# M7050X.net
KiCad netlist of a schematic drawn in EAGLE
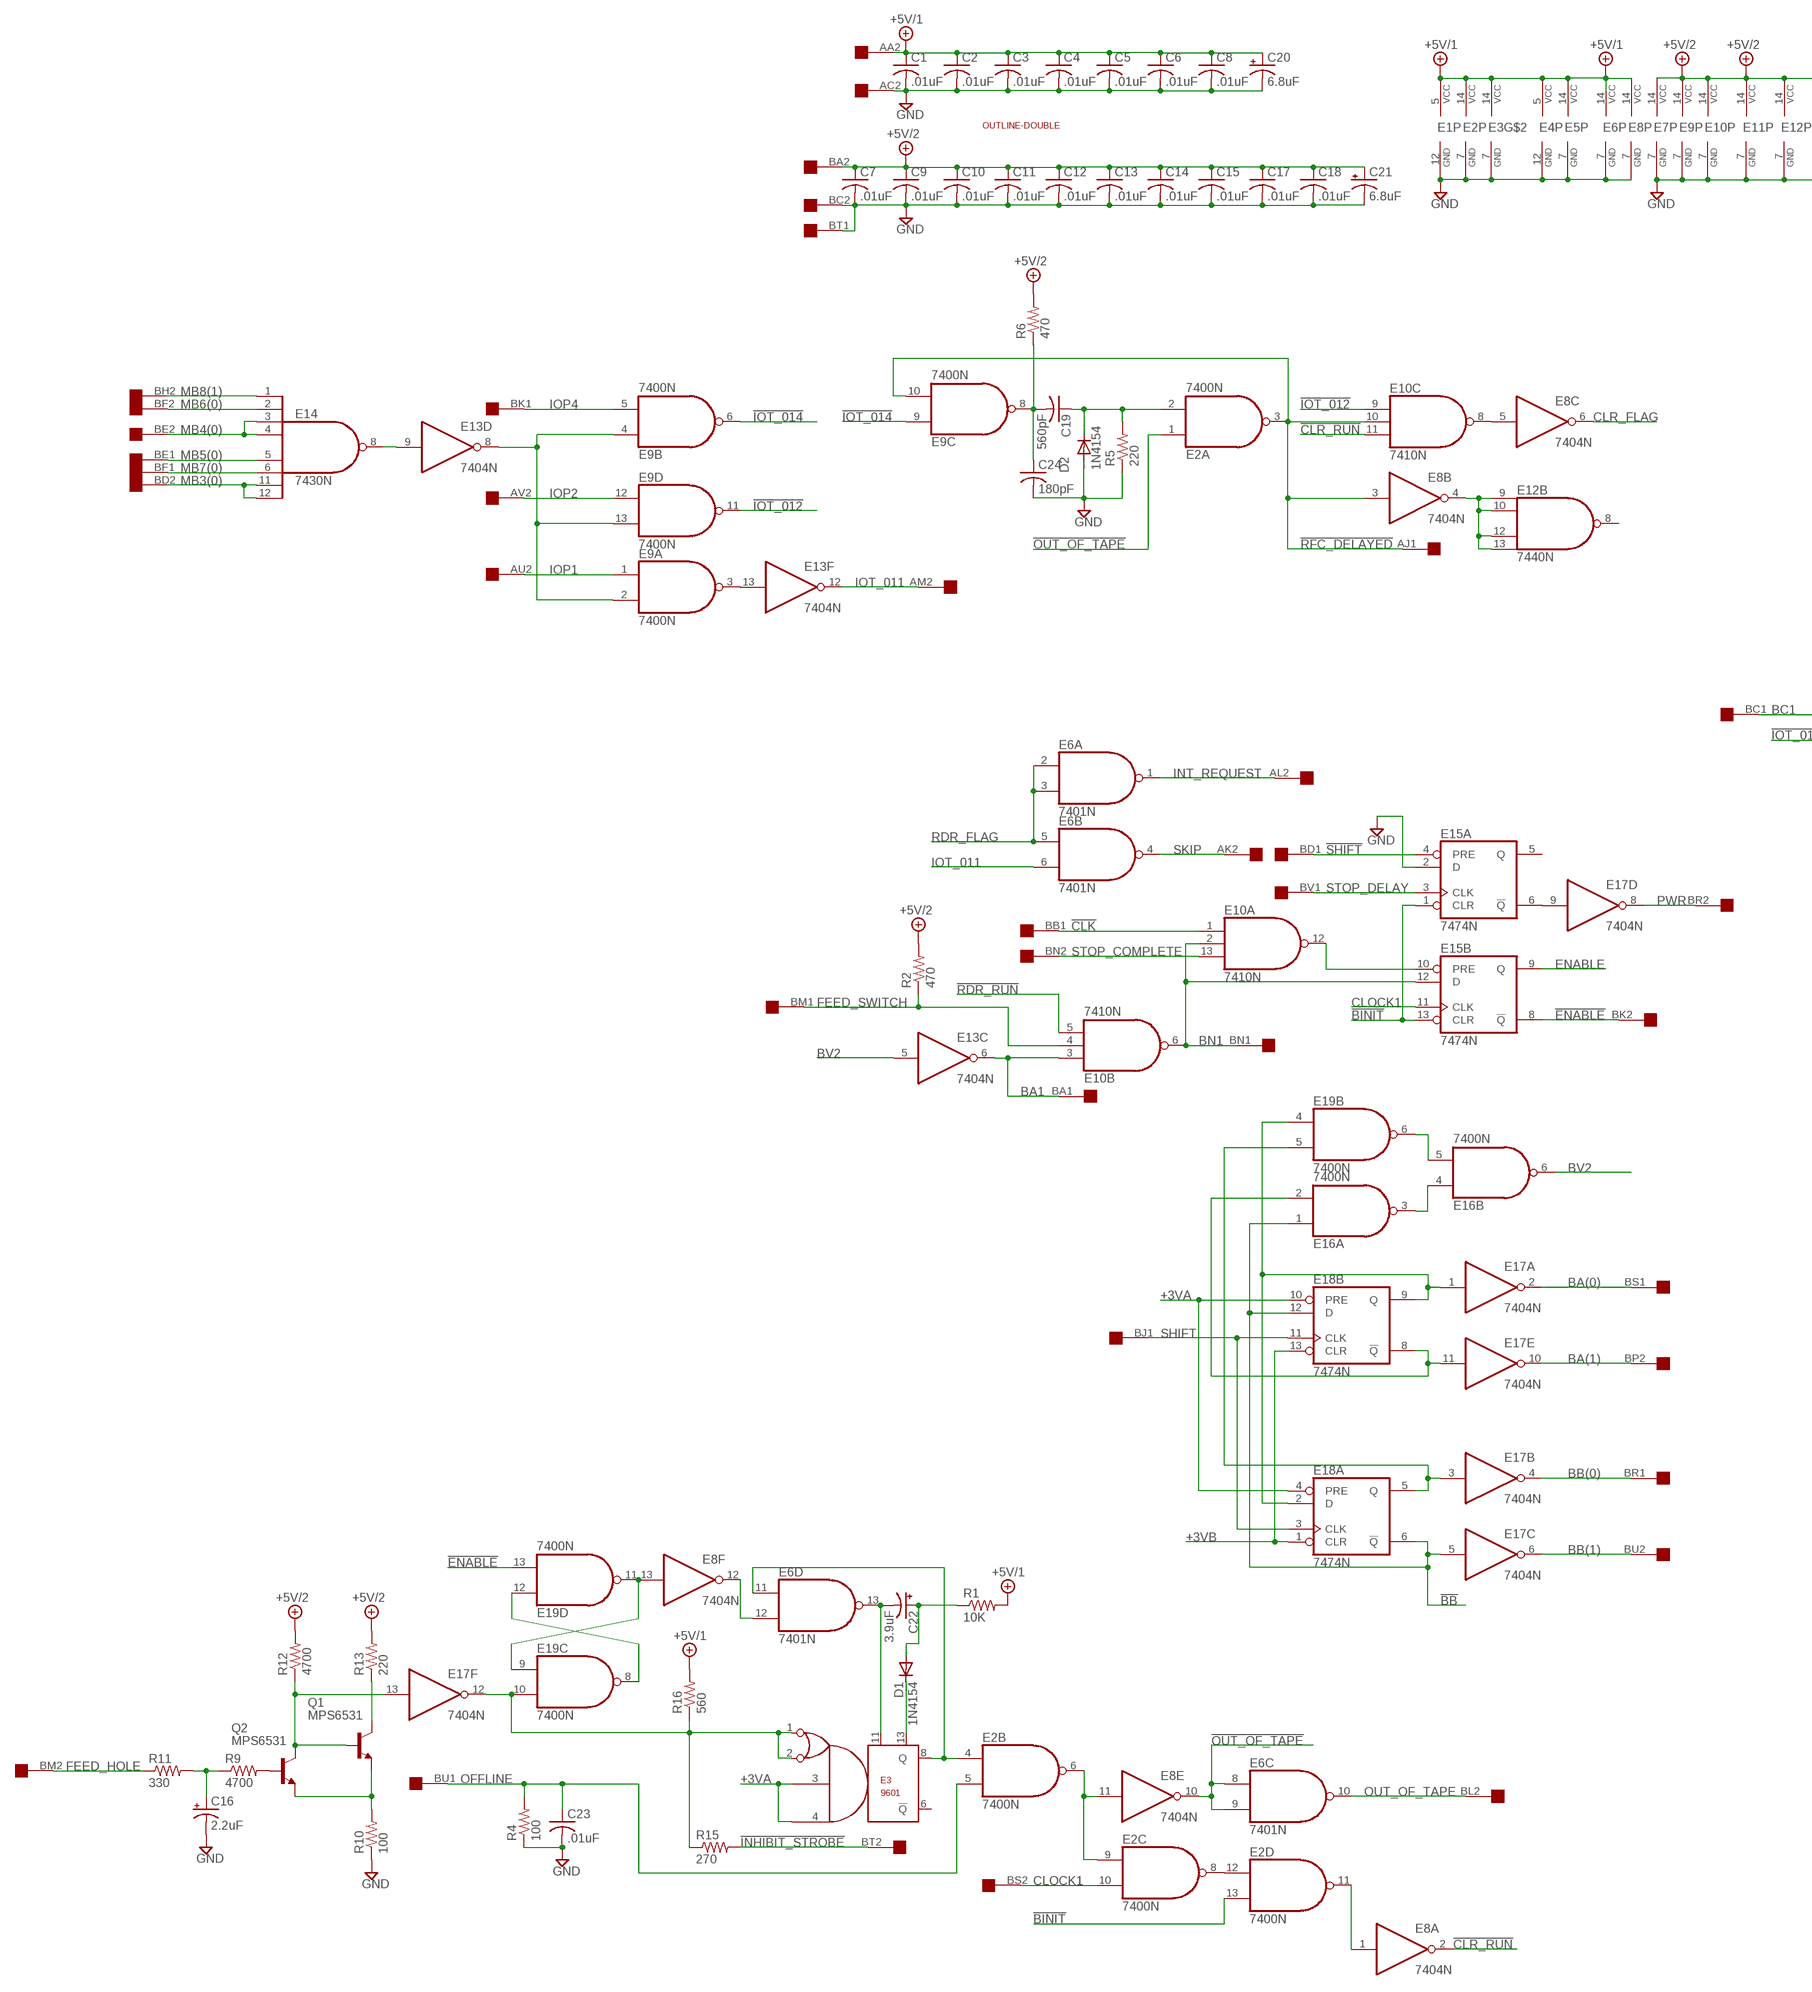
[diagram p0: schematic, sheet 1, part 1 of 2]
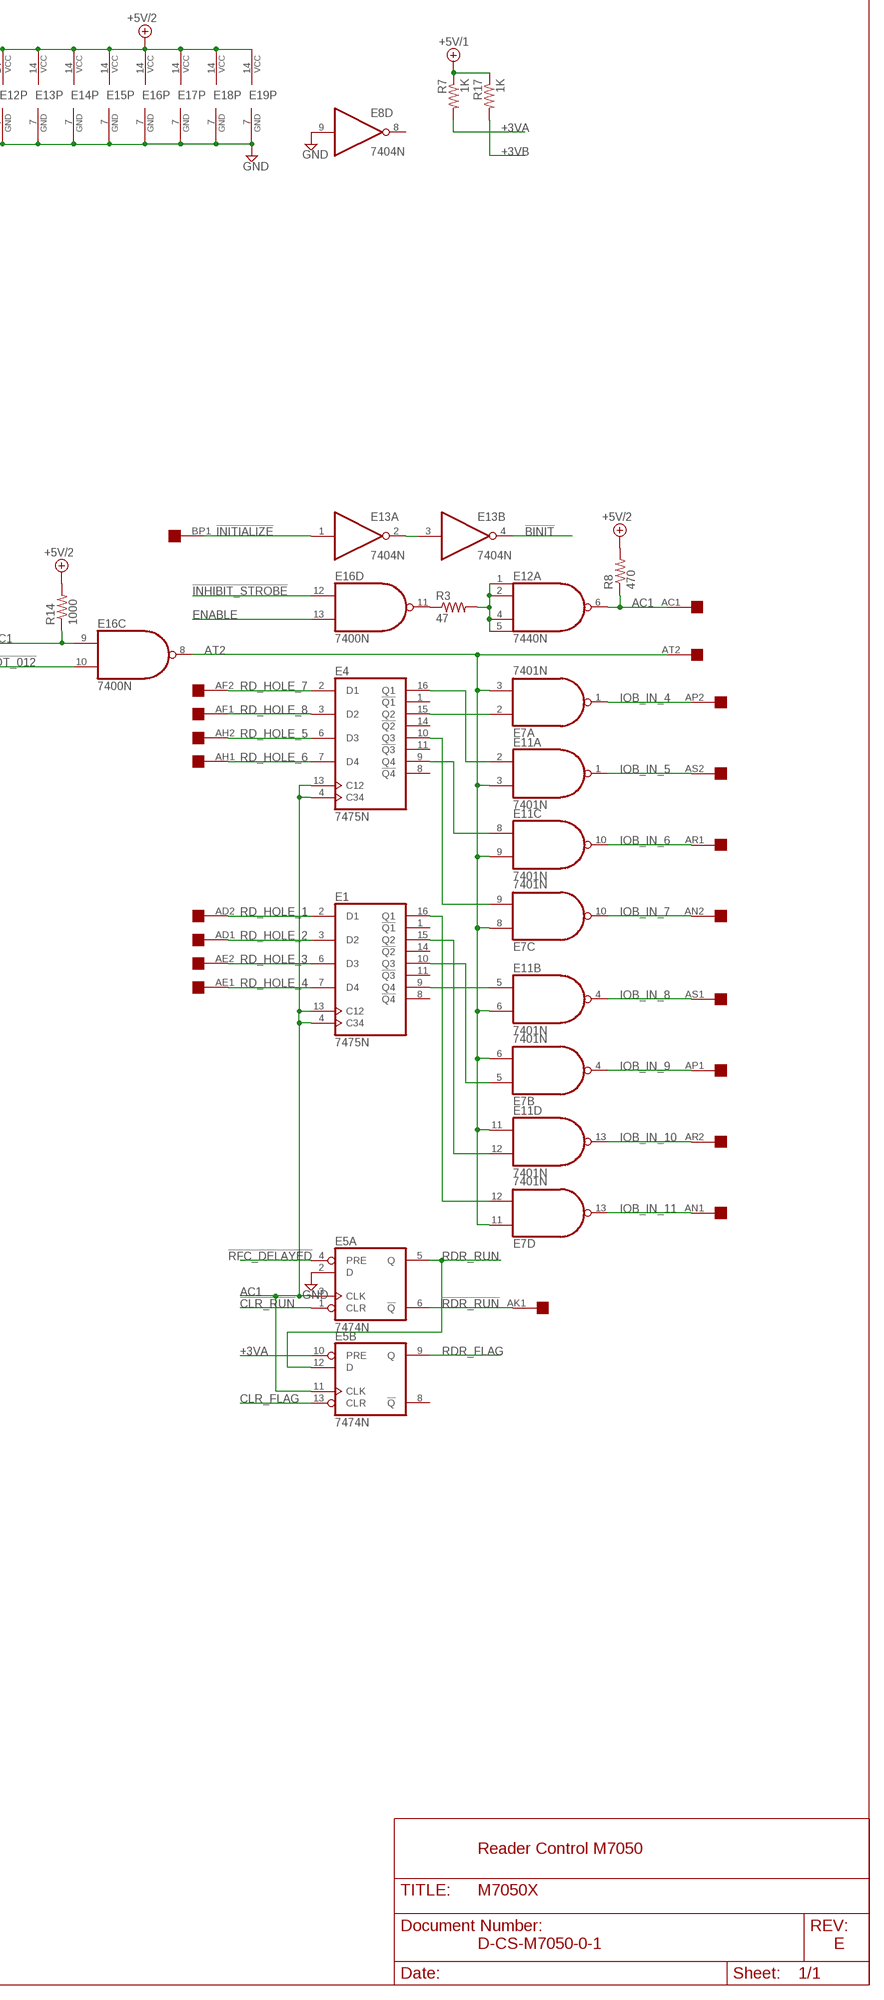
[diagram p1: schematic, sheet 1, part 2 of 2]

(export (version "E")
  (design (tool "Eeschema 10.0.6"))
  (components
    (comp (ref "C1")
      (value ".01uF")
      (footprint "eagle-import:C075-032X103")
      (libsource (lib "eagle-import") (part "C-US075-032X103"))
    )
    (comp (ref "C2")
      (value ".01uF")
      (footprint "eagle-import:C075-032X103")
      (libsource (lib "eagle-import") (part "C-US075-032X103"))
    )
    (comp (ref "C3")
      (value ".01uF")
      (footprint "eagle-import:C075-032X103")
      (libsource (lib "eagle-import") (part "C-US075-032X103"))
    )
    (comp (ref "C4")
      (value ".01uF")
      (footprint "eagle-import:C075-032X103")
      (libsource (lib "eagle-import") (part "C-US075-032X103"))
    )
    (comp (ref "C5")
      (value ".01uF")
      (footprint "eagle-import:C050-025X075")
      (libsource (lib "eagle-import") (part "C-US050-025X075"))
    )
    (comp (ref "C6")
      (value ".01uF")
      (footprint "eagle-import:C075-032X103")
      (libsource (lib "eagle-import") (part "C-US075-032X103"))
    )
    (comp (ref "C7")
      (value ".01uF")
      (footprint "eagle-import:C050-025X075")
      (libsource (lib "eagle-import") (part "C-US050-025X075"))
    )
    (comp (ref "C8")
      (value ".01uF")
      (footprint "eagle-import:C075-032X103")
      (libsource (lib "eagle-import") (part "C-US075-032X103"))
    )
    (comp (ref "C9")
      (value ".01uF")
      (footprint "eagle-import:C075-032X103")
      (libsource (lib "eagle-import") (part "C-US075-032X103"))
    )
    (comp (ref "C10")
      (value ".01uF")
      (footprint "eagle-import:C050-025X075")
      (libsource (lib "eagle-import") (part "C-US050-025X075"))
    )
    (comp (ref "C11")
      (value ".01uF")
      (footprint "eagle-import:C075-032X103")
      (libsource (lib "eagle-import") (part "C-US075-032X103"))
    )
    (comp (ref "C12")
      (value ".01uF")
      (footprint "eagle-import:C075-032X103")
      (libsource (lib "eagle-import") (part "C-US075-032X103"))
    )
    (comp (ref "C13")
      (value ".01uF")
      (footprint "eagle-import:C050-025X075")
      (libsource (lib "eagle-import") (part "C-US050-025X075"))
    )
    (comp (ref "C14")
      (value ".01uF")
      (footprint "eagle-import:C075-032X103")
      (libsource (lib "eagle-import") (part "C-US075-032X103"))
    )
    (comp (ref "C15")
      (value ".01uF")
      (footprint "eagle-import:C075-032X103")
      (libsource (lib "eagle-import") (part "C-US075-032X103"))
    )
    (comp (ref "C16")
      (value "2.2uF")
      (footprint "eagle-import:E12-8")
      (libsource (lib "eagle-import") (part "CPOL-USE20-8AXIAL"))
    )
    (comp (ref "C17")
      (value ".01uF")
      (footprint "eagle-import:C075-032X103")
      (libsource (lib "eagle-import") (part "C-US075-032X103"))
    )
    (comp (ref "C18")
      (value ".01uF")
      (footprint "eagle-import:C075-032X103")
      (libsource (lib "eagle-import") (part "C-US075-032X103"))
    )
    (comp (ref "C19")
      (value "560pF")
      (footprint "eagle-import:C050-025X075")
      (libsource (lib "eagle-import") (part "C-US050-025X075"))
    )
    (comp (ref "C20")
      (value "6.8uF")
      (footprint "eagle-import:E12-8")
      (libsource (lib "eagle-import") (part "CPOL-USE20-8AXIAL"))
    )
    (comp (ref "C21")
      (value "6.8uF")
      (footprint "eagle-import:E12-8")
      (libsource (lib "eagle-import") (part "CPOL-USE20-8AXIAL"))
    )
    (comp (ref "C22")
      (value "3.9uF")
      (footprint "eagle-import:E15-5")
      (libsource (lib "eagle-import") (part "CPOL-USE15-5AXIAL"))
    )
    (comp (ref "C23")
      (value ".01uF")
      (footprint "eagle-import:C075-032X103")
      (libsource (lib "eagle-import") (part "C-US075-032X103"))
    )
    (comp (ref "C24")
      (value "180pF")
      (footprint "eagle-import:C075-032X103")
      (libsource (lib "eagle-import") (part "C-US075-032X103"))
    )
    (comp (ref "D1")
      (value "1N4154")
      (footprint "eagle-import:DO35-10")
      (libsource (lib "eagle-import") (part "1N4148DO35-10"))
    )
    (comp (ref "D2")
      (value "1N4154")
      (footprint "eagle-import:DO35-10")
      (libsource (lib "eagle-import") (part "1N4148DO35-10"))
    )
    (comp (ref "E1")
      (value "7475N")
      (footprint "eagle-import:DIL16")
      (libsource (lib "eagle-import") (part "7475N"))
    )
    (comp (ref "E2")
      (value "7400N")
      (footprint "eagle-import:DIL14")
      (libsource (lib "eagle-import") (part "7400N"))
    )
    (comp (ref "E3")
      (value "9601")
      (footprint "eagle-import:DIL14")
      (libsource (lib "eagle-import") (part "9601"))
    )
    (comp (ref "E4")
      (value "7475N")
      (footprint "eagle-import:DIL16")
      (libsource (lib "eagle-import") (part "7475N"))
    )
    (comp (ref "E5")
      (value "7474N")
      (footprint "eagle-import:DIL14")
      (libsource (lib "eagle-import") (part "7474NS"))
    )
    (comp (ref "E6")
      (value "7401N")
      (footprint "eagle-import:DIL14")
      (libsource (lib "eagle-import") (part "7401NLS"))
    )
    (comp (ref "E7")
      (value "7401N")
      (footprint "eagle-import:DIL14")
      (libsource (lib "eagle-import") (part "7401NLS"))
    )
    (comp (ref "E8")
      (value "7404N")
      (footprint "eagle-import:DIL14")
      (libsource (lib "eagle-import") (part "7404N"))
    )
    (comp (ref "E9")
      (value "7400N")
      (footprint "eagle-import:DIL14")
      (libsource (lib "eagle-import") (part "7400N"))
    )
    (comp (ref "E10")
      (value "7410N")
      (footprint "eagle-import:DIL14")
      (libsource (lib "eagle-import") (part "7410N"))
    )
    (comp (ref "E11")
      (value "7401N")
      (footprint "eagle-import:DIL14")
      (libsource (lib "eagle-import") (part "7401NLS"))
    )
    (comp (ref "E12")
      (value "7440N")
      (footprint "eagle-import:DIL14")
      (libsource (lib "eagle-import") (part "7420NS"))
    )
    (comp (ref "E13")
      (value "7404N")
      (footprint "eagle-import:DIL14")
      (libsource (lib "eagle-import") (part "7404N"))
    )
    (comp (ref "E14")
      (value "7430N")
      (footprint "eagle-import:DIL14")
      (libsource (lib "eagle-import") (part "7430N"))
    )
    (comp (ref "E15")
      (value "7474N")
      (footprint "eagle-import:DIL14")
      (libsource (lib "eagle-import") (part "7474NS"))
    )
    (comp (ref "E16")
      (value "7400N")
      (footprint "eagle-import:DIL14")
      (libsource (lib "eagle-import") (part "7400N"))
    )
    (comp (ref "E17")
      (value "7404N")
      (footprint "eagle-import:DIL14")
      (libsource (lib "eagle-import") (part "7404N"))
    )
    (comp (ref "E18")
      (value "7474N")
      (footprint "eagle-import:DIL14")
      (libsource (lib "eagle-import") (part "7474NS"))
    )
    (comp (ref "E19")
      (value "7400N")
      (footprint "eagle-import:DIL14")
      (libsource (lib "eagle-import") (part "7400N"))
    )
    (comp (ref "Q1")
      (value "MPS6531")
      (footprint "eagle-import:TO5")
      (libsource (lib "eagle-import") (part "2N2102"))
    )
    (comp (ref "Q2")
      (value "MPS6531")
      (footprint "eagle-import:TO5")
      (libsource (lib "eagle-import") (part "2N2102"))
    )
    (comp (ref "R1")
      (value "10K")
      (footprint "eagle-import:0207_10")
      (libsource (lib "eagle-import") (part "R-US_0207/10"))
    )
    (comp (ref "R2")
      (value "470")
      (footprint "eagle-import:0207_10")
      (libsource (lib "eagle-import") (part "R-US_0207/10"))
    )
    (comp (ref "R3")
      (value "47")
      (footprint "eagle-import:0207_10")
      (libsource (lib "eagle-import") (part "R-US_0207/10"))
    )
    (comp (ref "R4")
      (value "100")
      (footprint "eagle-import:0207_10")
      (libsource (lib "eagle-import") (part "R-US_0207/10"))
    )
    (comp (ref "R5")
      (value "220")
      (footprint "eagle-import:0207_10")
      (libsource (lib "eagle-import") (part "R-US_0207/10"))
    )
    (comp (ref "R6")
      (value "470")
      (footprint "eagle-import:0207_10")
      (libsource (lib "eagle-import") (part "R-US_0207/10"))
    )
    (comp (ref "R7")
      (value "1K")
      (footprint "eagle-import:0207_10")
      (libsource (lib "eagle-import") (part "R-US_0207/10"))
    )
    (comp (ref "R8")
      (value "470")
      (footprint "eagle-import:0207_10")
      (libsource (lib "eagle-import") (part "R-US_0207/10"))
    )
    (comp (ref "R9")
      (value "4700")
      (footprint "eagle-import:0207_10")
      (libsource (lib "eagle-import") (part "R-US_0207/10"))
    )
    (comp (ref "R10")
      (value "100")
      (footprint "eagle-import:0207_10")
      (libsource (lib "eagle-import") (part "R-US_0207/10"))
    )
    (comp (ref "R11")
      (value "330")
      (footprint "eagle-import:0207_10")
      (libsource (lib "eagle-import") (part "R-US_0207/10"))
    )
    (comp (ref "R12")
      (value "4700")
      (footprint "eagle-import:0207_10")
      (libsource (lib "eagle-import") (part "R-US_0207/10"))
    )
    (comp (ref "R13")
      (value "220")
      (footprint "eagle-import:0207_10")
      (libsource (lib "eagle-import") (part "R-US_0207/10"))
    )
    (comp (ref "R14")
      (value "1000")
      (footprint "eagle-import:0207_10")
      (libsource (lib "eagle-import") (part "R-US_0207/10"))
    )
    (comp (ref "R15")
      (value "270")
      (footprint "eagle-import:0207_10")
      (libsource (lib "eagle-import") (part "R-US_0207/10"))
    )
    (comp (ref "R16")
      (value "560")
      (footprint "eagle-import:0207_10")
      (libsource (lib "eagle-import") (part "R-US_0207/10"))
    )
    (comp (ref "R17")
      (value "1K")
      (footprint "eagle-import:0207_10")
      (libsource (lib "eagle-import") (part "R-US_0207/10"))
    )
    (comp (ref "U$5")
      (value "DOUBLE")
      (footprint "eagle-import:EDGE-CON4")
      (libsource (lib "eagle-import") (part "DOUBLE"))
    )
    (comp (ref "U$6")
      (value "OUTLINE-DOUBLE")
      (footprint "eagle-import:DOUBLE")
      (libsource (lib "eagle-import") (part "OUTLINE-DOUBLE"))
    )
  )
  (nets
    (net (code "1") (name "+5V{slash}1") (class "Default")
      (node (ref "C1") (pin "1") (pinfunction "1_1") (pintype "passive"))
      (node (ref "C2") (pin "1") (pinfunction "1_1") (pintype "passive"))
      (node (ref "C20") (pin "+") (pinfunction "+_+") (pintype "passive"))
      (node (ref "C3") (pin "1") (pinfunction "1_1") (pintype "passive"))
      (node (ref "C4") (pin "1") (pinfunction "1_1") (pintype "passive"))
      (node (ref "C5") (pin "1") (pinfunction "1_1") (pintype "passive"))
      (node (ref "C6") (pin "1") (pinfunction "1_1") (pintype "passive"))
      (node (ref "C8") (pin "1") (pinfunction "1_1") (pintype "passive"))
      (node (ref "E1") (pin "5") (pinfunction "VCC_5") (pintype "power_in"))
      (node (ref "E2") (pin "14") (pinfunction "VCC_14") (pintype "power_in"))
      (node (ref "E3") (pin "14") (pinfunction "VCC_14") (pintype "power_in"))
      (node (ref "E4") (pin "5") (pinfunction "VCC_5") (pintype "power_in"))
      (node (ref "E5") (pin "14") (pinfunction "VCC_14") (pintype "power_in"))
      (node (ref "E6") (pin "14") (pinfunction "VCC_14") (pintype "power_in"))
      (node (ref "E8") (pin "14") (pinfunction "VCC_14") (pintype "power_in"))
      (node (ref "R1") (pin "2") (pinfunction "2_2") (pintype "passive"))
      (node (ref "R16") (pin "2") (pinfunction "2_2") (pintype "passive"))
      (node (ref "R17") (pin "1") (pinfunction "1_1") (pintype "passive"))
      (node (ref "R7") (pin "1") (pinfunction "1_1") (pintype "passive"))
      (node (ref "U$5") (pin "AA2") (pinfunction "1_AA2") (pintype "bidirectional"))
    )
    (net (code "2") (name "+5V{slash}2") (class "Default")
      (node (ref "C10") (pin "1") (pinfunction "1_1") (pintype "passive"))
      (node (ref "C11") (pin "1") (pinfunction "1_1") (pintype "passive"))
      (node (ref "C12") (pin "1") (pinfunction "1_1") (pintype "passive"))
      (node (ref "C13") (pin "1") (pinfunction "1_1") (pintype "passive"))
      (node (ref "C14") (pin "1") (pinfunction "1_1") (pintype "passive"))
      (node (ref "C15") (pin "1") (pinfunction "1_1") (pintype "passive"))
      (node (ref "C17") (pin "1") (pinfunction "1_1") (pintype "passive"))
      (node (ref "C18") (pin "1") (pinfunction "1_1") (pintype "passive"))
      (node (ref "C21") (pin "+") (pinfunction "+_+") (pintype "passive"))
      (node (ref "C7") (pin "1") (pinfunction "1_1") (pintype "passive"))
      (node (ref "C9") (pin "1") (pinfunction "1_1") (pintype "passive"))
      (node (ref "E10") (pin "14") (pinfunction "VCC_14") (pintype "power_in"))
      (node (ref "E11") (pin "14") (pinfunction "VCC_14") (pintype "power_in"))
      (node (ref "E12") (pin "14") (pinfunction "VCC_14") (pintype "power_in"))
      (node (ref "E13") (pin "14") (pinfunction "VCC_14") (pintype "power_in"))
      (node (ref "E14") (pin "14") (pinfunction "VCC_14") (pintype "power_in"))
      (node (ref "E15") (pin "14") (pinfunction "VCC_14") (pintype "power_in"))
      (node (ref "E16") (pin "14") (pinfunction "VCC_14") (pintype "power_in"))
      (node (ref "E17") (pin "14") (pinfunction "VCC_14") (pintype "power_in"))
      (node (ref "E18") (pin "14") (pinfunction "VCC_14") (pintype "power_in"))
      (node (ref "E19") (pin "14") (pinfunction "VCC_14") (pintype "power_in"))
      (node (ref "E7") (pin "14") (pinfunction "VCC_14") (pintype "power_in"))
      (node (ref "E9") (pin "14") (pinfunction "VCC_14") (pintype "power_in"))
      (node (ref "R12") (pin "2") (pinfunction "2_2") (pintype "passive"))
      (node (ref "R13") (pin "2") (pinfunction "2_2") (pintype "passive"))
      (node (ref "R14") (pin "2") (pinfunction "2_2") (pintype "passive"))
      (node (ref "R2") (pin "2") (pinfunction "2_2") (pintype "passive"))
      (node (ref "R6") (pin "2") (pinfunction "2_2") (pintype "passive"))
      (node (ref "R8") (pin "2") (pinfunction "2_2") (pintype "passive"))
      (node (ref "U$5") (pin "BA2") (pinfunction "1_BA2") (pintype "bidirectional"))
    )
    (net (code "3") (name "/+3VA") (class "Default")
      (node (ref "E18") (pin "10") (pinfunction "PRE_10") (pintype "input"))
      (node (ref "E18") (pin "4") (pinfunction "PRE_4") (pintype "input"))
      (node (ref "E3") (pin "3") (pinfunction "P$3_3") (pintype "input"))
      (node (ref "E3") (pin "4") (pinfunction "P$4_4") (pintype "input"))
      (node (ref "E5") (pin "10") (pinfunction "PRE_10") (pintype "input"))
      (node (ref "R7") (pin "2") (pinfunction "2_2") (pintype "passive"))
    )
    (net (code "4") (name "/+3VB") (class "Default")
      (node (ref "E18") (pin "1") (pinfunction "CLR_1") (pintype "input"))
      (node (ref "E18") (pin "13") (pinfunction "CLR_13") (pintype "input"))
      (node (ref "R17") (pin "2") (pinfunction "2_2") (pintype "passive"))
    )
    (net (code "5") (name "/AC1") (class "Default")
      (node (ref "E1") (pin "13") (pinfunction "C12_13") (pintype "input"))
      (node (ref "E1") (pin "4") (pinfunction "C34_4") (pintype "input"))
      (node (ref "E12") (pin "6") (pinfunction "O_6") (pintype "output"))
      (node (ref "E4") (pin "13") (pinfunction "C12_13") (pintype "input"))
      (node (ref "E4") (pin "4") (pinfunction "C34_4") (pintype "input"))
      (node (ref "E5") (pin "11") (pinfunction "CLK_11") (pintype "input"))
      (node (ref "E5") (pin "3") (pinfunction "CLK_3") (pintype "input"))
      (node (ref "R8") (pin "1") (pinfunction "1_1") (pintype "passive"))
      (node (ref "U$5") (pin "AC1") (pinfunction "1_AC1") (pintype "bidirectional"))
    )
    (net (code "6") (name "/AT2") (class "Default")
      (node (ref "E11") (pin "11") (pinfunction "I0_11") (pintype "input"))
      (node (ref "E11") (pin "3") (pinfunction "I1_3") (pintype "input"))
      (node (ref "E11") (pin "6") (pinfunction "I1_6") (pintype "input"))
      (node (ref "E11") (pin "9") (pinfunction "I1_9") (pintype "input"))
      (node (ref "E16") (pin "8") (pinfunction "O_8") (pintype "output"))
      (node (ref "E7") (pin "11") (pinfunction "I0_11") (pintype "input"))
      (node (ref "E7") (pin "3") (pinfunction "I1_3") (pintype "input"))
      (node (ref "E7") (pin "6") (pinfunction "I1_6") (pintype "input"))
      (node (ref "E7") (pin "8") (pinfunction "I0_8") (pintype "input"))
      (node (ref "U$5") (pin "AT2") (pinfunction "1_AT2") (pintype "bidirectional"))
    )
    (net (code "7") (name "/BA(0)") (class "Default")
      (node (ref "E17") (pin "2") (pinfunction "O_2") (pintype "output"))
      (node (ref "U$5") (pin "BS1") (pinfunction "1_BS1") (pintype "bidirectional"))
    )
    (net (code "8") (name "/BA(1)") (class "Default")
      (node (ref "E17") (pin "10") (pinfunction "O_10") (pintype "output"))
      (node (ref "U$5") (pin "BP2") (pinfunction "1_BP2") (pintype "bidirectional"))
    )
    (net (code "9") (name "/BA1") (class "Default")
      (node (ref "E10") (pin "3") (pinfunction "I0_3") (pintype "input"))
      (node (ref "E13") (pin "6") (pinfunction "O_6") (pintype "output"))
      (node (ref "U$5") (pin "BA1") (pinfunction "1_BA1") (pintype "bidirectional"))
    )
    (net (code "10") (name "/BB(0)") (class "Default")
      (node (ref "E17") (pin "4") (pinfunction "O_4") (pintype "output"))
      (node (ref "U$5") (pin "BR1") (pinfunction "1_BR1") (pintype "bidirectional"))
    )
    (net (code "11") (name "/BB(1)") (class "Default")
      (node (ref "E17") (pin "6") (pinfunction "O_6") (pintype "output"))
      (node (ref "U$5") (pin "BU2") (pinfunction "1_BU2") (pintype "bidirectional"))
    )
    (net (code "12") (name "/BC1") (class "Default")
      (node (ref "E16") (pin "9") (pinfunction "I0_9") (pintype "input"))
      (node (ref "R14") (pin "1") (pinfunction "1_1") (pintype "passive"))
      (node (ref "U$5") (pin "BC1") (pinfunction "1_BC1") (pintype "bidirectional"))
    )
    (net (code "13") (name "/BN1") (class "Default")
      (node (ref "E10") (pin "2") (pinfunction "I1_2") (pintype "input"))
      (node (ref "E10") (pin "6") (pinfunction "O_6") (pintype "output"))
      (node (ref "E15") (pin "12") (pinfunction "D_12") (pintype "input"))
      (node (ref "U$5") (pin "BN1") (pinfunction "1_BN1") (pintype "bidirectional"))
    )
    (net (code "14") (name "/BV2") (class "Default")
      (node (ref "E13") (pin "5") (pinfunction "I_5") (pintype "input"))
      (node (ref "E16") (pin "6") (pinfunction "O_6") (pintype "output"))
    )
    (net (code "15") (name "/CLOCK1") (class "Default")
      (node (ref "E15") (pin "11") (pinfunction "CLK_11") (pintype "input"))
      (node (ref "E2") (pin "10") (pinfunction "I1_10") (pintype "input"))
      (node (ref "U$5") (pin "BS2") (pinfunction "1_BS2") (pintype "bidirectional"))
    )
    (net (code "16") (name "/CLR_FLAG") (class "Default")
      (node (ref "E5") (pin "13") (pinfunction "CLR_13") (pintype "input"))
      (node (ref "E8") (pin "6") (pinfunction "O_6") (pintype "output"))
    )
    (net (code "17") (name "/ENABLE") (class "Default")
      (node (ref "E15") (pin "9") (pinfunction "Q_9") (pintype "output"))
      (node (ref "E16") (pin "13") (pinfunction "I1_13") (pintype "input"))
    )
    (net (code "18") (name "/FEED_HOLE") (class "Default")
      (node (ref "R11") (pin "1") (pinfunction "1_1") (pintype "passive"))
      (node (ref "U$5") (pin "BM2") (pinfunction "1_BM2") (pintype "bidirectional"))
    )
    (net (code "19") (name "/FEED_SWITCH") (class "Default")
      (node (ref "E10") (pin "4") (pinfunction "I1_4") (pintype "input"))
      (node (ref "R2") (pin "1") (pinfunction "1_1") (pintype "passive"))
      (node (ref "U$5") (pin "BM1") (pinfunction "1_BM1") (pintype "bidirectional"))
    )
    (net (code "20") (name "/INT_REQUEST") (class "Default")
      (node (ref "E6") (pin "1") (pinfunction "O_1") (pintype "open_collector"))
      (node (ref "U$5") (pin "AL2") (pinfunction "1_AL2") (pintype "bidirectional"))
    )
    (net (code "21") (name "/IOB_IN_4") (class "Default")
      (node (ref "E7") (pin "1") (pinfunction "O_1") (pintype "open_collector"))
      (node (ref "U$5") (pin "AP2") (pinfunction "1_AP2") (pintype "bidirectional"))
    )
    (net (code "22") (name "/IOB_IN_5") (class "Default")
      (node (ref "E11") (pin "1") (pinfunction "O_1") (pintype "open_collector"))
      (node (ref "U$5") (pin "AS2") (pinfunction "1_AS2") (pintype "bidirectional"))
    )
    (net (code "23") (name "/IOB_IN_6") (class "Default")
      (node (ref "E11") (pin "10") (pinfunction "O_10") (pintype "open_collector"))
      (node (ref "U$5") (pin "AR1") (pinfunction "1_AR1") (pintype "bidirectional"))
    )
    (net (code "24") (name "/IOB_IN_7") (class "Default")
      (node (ref "E7") (pin "10") (pinfunction "O_10") (pintype "open_collector"))
      (node (ref "U$5") (pin "AN2") (pinfunction "1_AN2") (pintype "bidirectional"))
    )
    (net (code "25") (name "/IOB_IN_8") (class "Default")
      (node (ref "E11") (pin "4") (pinfunction "O_4") (pintype "open_collector"))
      (node (ref "U$5") (pin "AS1") (pinfunction "1_AS1") (pintype "bidirectional"))
    )
    (net (code "26") (name "/IOB_IN_9") (class "Default")
      (node (ref "E7") (pin "4") (pinfunction "O_4") (pintype "open_collector"))
      (node (ref "U$5") (pin "AP1") (pinfunction "1_AP1") (pintype "bidirectional"))
    )
    (net (code "27") (name "/IOB_IN_10") (class "Default")
      (node (ref "E11") (pin "13") (pinfunction "O_13") (pintype "open_collector"))
      (node (ref "U$5") (pin "AR2") (pinfunction "1_AR2") (pintype "bidirectional"))
    )
    (net (code "28") (name "/IOB_IN_11") (class "Default")
      (node (ref "E7") (pin "13") (pinfunction "O_13") (pintype "open_collector"))
      (node (ref "U$5") (pin "AN1") (pinfunction "1_AN1") (pintype "bidirectional"))
    )
    (net (code "29") (name "/IOP1") (class "Default")
      (node (ref "E9") (pin "1") (pinfunction "I0_1") (pintype "input"))
      (node (ref "U$5") (pin "AU2") (pinfunction "1_AU2") (pintype "bidirectional"))
    )
    (net (code "30") (name "/IOP2") (class "Default")
      (node (ref "E9") (pin "12") (pinfunction "I0_12") (pintype "input"))
      (node (ref "U$5") (pin "AV2") (pinfunction "1_AV2") (pintype "bidirectional"))
    )
    (net (code "31") (name "/IOP4") (class "Default")
      (node (ref "E9") (pin "5") (pinfunction "I1_5") (pintype "input"))
      (node (ref "U$5") (pin "BK1") (pinfunction "1_BK1") (pintype "bidirectional"))
    )
    (net (code "32") (name "/IOT_011") (class "Default")
      (node (ref "E13") (pin "12") (pinfunction "O_12") (pintype "output"))
      (node (ref "E6") (pin "6") (pinfunction "I1_6") (pintype "input"))
      (node (ref "U$5") (pin "AM2") (pinfunction "1_AM2") (pintype "bidirectional"))
    )
    (net (code "33") (name "/MB3(0)") (class "Default")
      (node (ref "E14") (pin "11") (pinfunction "I6_11") (pintype "input"))
      (node (ref "E14") (pin "12") (pinfunction "I7_12") (pintype "input"))
      (node (ref "U$5") (pin "BD2") (pinfunction "1_BD2") (pintype "bidirectional"))
    )
    (net (code "34") (name "/MB4(0)") (class "Default")
      (node (ref "E14") (pin "3") (pinfunction "I2_3") (pintype "input"))
      (node (ref "E14") (pin "4") (pinfunction "I3_4") (pintype "input"))
      (node (ref "U$5") (pin "BE2") (pinfunction "1_BE2") (pintype "bidirectional"))
    )
    (net (code "35") (name "/MB5(0)") (class "Default")
      (node (ref "E14") (pin "5") (pinfunction "I4_5") (pintype "input"))
      (node (ref "U$5") (pin "BE1") (pinfunction "1_BE1") (pintype "bidirectional"))
    )
    (net (code "36") (name "/MB6(0)") (class "Default")
      (node (ref "E14") (pin "2") (pinfunction "I1_2") (pintype "input"))
      (node (ref "U$5") (pin "BF2") (pinfunction "1_BF2") (pintype "bidirectional"))
    )
    (net (code "37") (name "/MB7(0)") (class "Default")
      (node (ref "E14") (pin "6") (pinfunction "I5_6") (pintype "input"))
      (node (ref "U$5") (pin "BF1") (pinfunction "1_BF1") (pintype "bidirectional"))
    )
    (net (code "38") (name "/MB8(1)") (class "Default")
      (node (ref "E14") (pin "1") (pinfunction "I0_1") (pintype "input"))
      (node (ref "U$5") (pin "BH2") (pinfunction "1_BH2") (pintype "bidirectional"))
    )
    (net (code "39") (name "/OFFLINE") (class "Default")
      (node (ref "C23") (pin "1") (pinfunction "1_1") (pintype "passive"))
      (node (ref "E2") (pin "5") (pinfunction "I1_5") (pintype "input"))
      (node (ref "R4") (pin "2") (pinfunction "2_2") (pintype "passive"))
      (node (ref "U$5") (pin "BU1") (pinfunction "1_BU1") (pintype "bidirectional"))
    )
    (net (code "40") (name "/OUT_OF_TAPE") (class "Default")
      (node (ref "E6") (pin "10") (pinfunction "O_10") (pintype "open_collector"))
      (node (ref "U$5") (pin "BL2") (pinfunction "1_BL2") (pintype "bidirectional"))
    )
    (net (code "41") (name "/PWR") (class "Default")
      (node (ref "E17") (pin "8") (pinfunction "O_8") (pintype "output"))
      (node (ref "U$5") (pin "BR2") (pinfunction "1_BR2") (pintype "bidirectional"))
    )
    (net (code "42") (name "/RDR_FLAG") (class "Default")
      (node (ref "E5") (pin "9") (pinfunction "Q_9") (pintype "output"))
      (node (ref "E6") (pin "2") (pinfunction "I0_2") (pintype "input"))
      (node (ref "E6") (pin "3") (pinfunction "I1_3") (pintype "input"))
      (node (ref "E6") (pin "5") (pinfunction "I0_5") (pintype "input"))
    )
    (net (code "43") (name "/RDR_RUN") (class "Default")
      (node (ref "E5") (pin "12") (pinfunction "D_12") (pintype "input"))
      (node (ref "E5") (pin "5") (pinfunction "Q_5") (pintype "output"))
    )
    (net (code "44") (name "/RD_HOLE_1") (class "Default")
      (node (ref "E1") (pin "2") (pinfunction "D1_2") (pintype "input"))
      (node (ref "U$5") (pin "AD2") (pinfunction "1_AD2") (pintype "bidirectional"))
    )
    (net (code "45") (name "/RD_HOLE_2") (class "Default")
      (node (ref "E1") (pin "3") (pinfunction "D2_3") (pintype "input"))
      (node (ref "U$5") (pin "AD1") (pinfunction "1_AD1") (pintype "bidirectional"))
    )
    (net (code "46") (name "/RD_HOLE_3") (class "Default")
      (node (ref "E1") (pin "6") (pinfunction "D3_6") (pintype "input"))
      (node (ref "U$5") (pin "AE2") (pinfunction "1_AE2") (pintype "bidirectional"))
    )
    (net (code "47") (name "/RD_HOLE_4") (class "Default")
      (node (ref "E1") (pin "7") (pinfunction "D4_7") (pintype "input"))
      (node (ref "U$5") (pin "AE1") (pinfunction "1_AE1") (pintype "bidirectional"))
    )
    (net (code "48") (name "/RD_HOLE_5") (class "Default")
      (node (ref "E4") (pin "6") (pinfunction "D3_6") (pintype "input"))
      (node (ref "U$5") (pin "AH2") (pinfunction "1_AH2") (pintype "bidirectional"))
    )
    (net (code "49") (name "/RD_HOLE_6") (class "Default")
      (node (ref "E4") (pin "7") (pinfunction "D4_7") (pintype "input"))
      (node (ref "U$5") (pin "AH1") (pinfunction "1_AH1") (pintype "bidirectional"))
    )
    (net (code "50") (name "/RD_HOLE_7") (class "Default")
      (node (ref "E4") (pin "2") (pinfunction "D1_2") (pintype "input"))
      (node (ref "U$5") (pin "AF2") (pinfunction "1_AF2") (pintype "bidirectional"))
    )
    (net (code "51") (name "/RD_HOLE_8") (class "Default")
      (node (ref "E4") (pin "3") (pinfunction "D2_3") (pintype "input"))
      (node (ref "U$5") (pin "AF1") (pinfunction "1_AF1") (pintype "bidirectional"))
    )
    (net (code "52") (name "/SHIFT") (class "Default")
      (node (ref "E18") (pin "11") (pinfunction "CLK_11") (pintype "input"))
      (node (ref "E18") (pin "3") (pinfunction "CLK_3") (pintype "input"))
      (node (ref "U$5") (pin "BJ1") (pinfunction "1_BJ1") (pintype "bidirectional"))
    )
    (net (code "53") (name "/SKIP") (class "Default")
      (node (ref "E6") (pin "4") (pinfunction "O_4") (pintype "open_collector"))
      (node (ref "U$5") (pin "AK2") (pinfunction "1_AK2") (pintype "bidirectional"))
    )
    (net (code "54") (name "/STOP_COMPLETE") (class "Default")
      (node (ref "E10") (pin "13") (pinfunction "I2_13") (pintype "input"))
      (node (ref "U$5") (pin "BN2") (pinfunction "1_BN2") (pintype "bidirectional"))
    )
    (net (code "55") (name "/STOP_DELAY") (class "Default")
      (node (ref "E15") (pin "3") (pinfunction "CLK_3") (pintype "input"))
      (node (ref "U$5") (pin "BV1") (pinfunction "1_BV1") (pintype "bidirectional"))
    )
    (net (code "56") (name "/~{BB}") (class "Default")
      (node (ref "E16") (pin "1") (pinfunction "I0_1") (pintype "input"))
      (node (ref "E17") (pin "5") (pinfunction "I_5") (pintype "input"))
      (node (ref "E18") (pin "12") (pinfunction "D_12") (pintype "input"))
      (node (ref "E18") (pin "6") (pinfunction "~{Q}_6") (pintype "output"))
    )
    (net (code "57") (name "/~{BINIT}") (class "Default")
      (node (ref "E13") (pin "4") (pinfunction "O_4") (pintype "output"))
      (node (ref "E15") (pin "1") (pinfunction "CLR_1") (pintype "input"))
      (node (ref "E15") (pin "13") (pinfunction "CLR_13") (pintype "input"))
      (node (ref "E2") (pin "13") (pinfunction "I1_13") (pintype "input"))
    )
    (net (code "58") (name "/~{CLK}") (class "Default")
      (node (ref "E10") (pin "1") (pinfunction "I0_1") (pintype "input"))
      (node (ref "U$5") (pin "BB1") (pinfunction "1_BB1") (pintype "bidirectional"))
    )
    (net (code "59") (name "/~{CLR_RUN}") (class "Default")
      (node (ref "E10") (pin "11") (pinfunction "I2_11") (pintype "input"))
      (node (ref "E5") (pin "1") (pinfunction "CLR_1") (pintype "input"))
      (node (ref "E8") (pin "2") (pinfunction "O_2") (pintype "output"))
    )
    (net (code "60") (name "/~{ENABLE}") (class "Default")
      (node (ref "E15") (pin "8") (pinfunction "~{Q}_8") (pintype "output"))
      (node (ref "E19") (pin "13") (pinfunction "I1_13") (pintype "input"))
      (node (ref "U$5") (pin "BK2") (pinfunction "1_BK2") (pintype "bidirectional"))
    )
    (net (code "61") (name "/~{INHIBIT_STROBE}") (class "Default")
      (node (ref "E16") (pin "12") (pinfunction "I0_12") (pintype "input"))
      (node (ref "R15") (pin "2") (pinfunction "2_2") (pintype "passive"))
      (node (ref "U$5") (pin "BT2") (pinfunction "1_BT2") (pintype "bidirectional"))
    )
    (net (code "62") (name "/~{INITIALIZE}") (class "Default")
      (node (ref "E13") (pin "1") (pinfunction "I_1") (pintype "input"))
      (node (ref "U$5") (pin "BP1") (pinfunction "1_BP1") (pintype "bidirectional"))
    )
    (net (code "63") (name "/~{IOT_012}") (class "Default")
      (node (ref "E10") (pin "9") (pinfunction "I0_9") (pintype "input"))
      (node (ref "E16") (pin "10") (pinfunction "I1_10") (pintype "input"))
      (node (ref "E9") (pin "11") (pinfunction "O_11") (pintype "output"))
    )
    (net (code "64") (name "/~{IOT_014}") (class "Default")
      (node (ref "E9") (pin "6") (pinfunction "O_6") (pintype "output"))
      (node (ref "E9") (pin "9") (pinfunction "I0_9") (pintype "input"))
    )
    (net (code "65") (name "/~{OUT_OF_TAPE}") (class "Default")
      (node (ref "E2") (pin "1") (pinfunction "I0_1") (pintype "input"))
      (node (ref "E6") (pin "8") (pinfunction "I0_8") (pintype "input"))
      (node (ref "E6") (pin "9") (pinfunction "I1_9") (pintype "input"))
      (node (ref "E8") (pin "10") (pinfunction "O_10") (pintype "output"))
    )
    (net (code "66") (name "/~{RDR_RUN}") (class "Default")
      (node (ref "E10") (pin "5") (pinfunction "I2_5") (pintype "input"))
      (node (ref "E5") (pin "6") (pinfunction "~{Q}_6") (pintype "output"))
      (node (ref "U$5") (pin "AK1") (pinfunction "1_AK1") (pintype "bidirectional"))
    )
    (net (code "67") (name "/~{RFC_DELAYED}") (class "Default")
      (node (ref "E10") (pin "10") (pinfunction "I1_10") (pintype "input"))
      (node (ref "E2") (pin "3") (pinfunction "O_3") (pintype "output"))
      (node (ref "E5") (pin "4") (pinfunction "PRE_4") (pintype "input"))
      (node (ref "E8") (pin "3") (pinfunction "I_3") (pintype "input"))
      (node (ref "E9") (pin "10") (pinfunction "I1_10") (pintype "input"))
      (node (ref "U$5") (pin "AJ1") (pinfunction "1_AJ1") (pintype "bidirectional"))
    )
    (net (code "68") (name "/~{SHIFT}") (class "Default")
      (node (ref "E15") (pin "4") (pinfunction "PRE_4") (pintype "input"))
      (node (ref "U$5") (pin "BD1") (pinfunction "1_BD1") (pintype "bidirectional"))
    )
    (net (code "69") (name "GND") (class "Default")
      (node (ref "C1") (pin "2") (pinfunction "2_2") (pintype "passive"))
      (node (ref "C10") (pin "2") (pinfunction "2_2") (pintype "passive"))
      (node (ref "C11") (pin "2") (pinfunction "2_2") (pintype "passive"))
      (node (ref "C12") (pin "2") (pinfunction "2_2") (pintype "passive"))
      (node (ref "C13") (pin "2") (pinfunction "2_2") (pintype "passive"))
      (node (ref "C14") (pin "2") (pinfunction "2_2") (pintype "passive"))
      (node (ref "C15") (pin "2") (pinfunction "2_2") (pintype "passive"))
      (node (ref "C16") (pin "-") (pinfunction "-_-") (pintype "passive"))
      (node (ref "C17") (pin "2") (pinfunction "2_2") (pintype "passive"))
      (node (ref "C18") (pin "2") (pinfunction "2_2") (pintype "passive"))
      (node (ref "C2") (pin "2") (pinfunction "2_2") (pintype "passive"))
      (node (ref "C20") (pin "-") (pinfunction "-_-") (pintype "passive"))
      (node (ref "C21") (pin "-") (pinfunction "-_-") (pintype "passive"))
      (node (ref "C23") (pin "2") (pinfunction "2_2") (pintype "passive"))
      (node (ref "C24") (pin "2") (pinfunction "2_2") (pintype "passive"))
      (node (ref "C3") (pin "2") (pinfunction "2_2") (pintype "passive"))
      (node (ref "C4") (pin "2") (pinfunction "2_2") (pintype "passive"))
      (node (ref "C5") (pin "2") (pinfunction "2_2") (pintype "passive"))
      (node (ref "C6") (pin "2") (pinfunction "2_2") (pintype "passive"))
      (node (ref "C7") (pin "2") (pinfunction "2_2") (pintype "passive"))
      (node (ref "C8") (pin "2") (pinfunction "2_2") (pintype "passive"))
      (node (ref "C9") (pin "2") (pinfunction "2_2") (pintype "passive"))
      (node (ref "D2") (pin "A") (pinfunction "A_A") (pintype "passive"))
      (node (ref "E1") (pin "12") (pinfunction "GND_12") (pintype "power_in"))
      (node (ref "E10") (pin "7") (pinfunction "GND_7") (pintype "power_in"))
      (node (ref "E11") (pin "7") (pinfunction "GND_7") (pintype "power_in"))
      (node (ref "E12") (pin "7") (pinfunction "GND_7") (pintype "power_in"))
      (node (ref "E13") (pin "7") (pinfunction "GND_7") (pintype "power_in"))
      (node (ref "E14") (pin "7") (pinfunction "GND_7") (pintype "power_in"))
      (node (ref "E15") (pin "2") (pinfunction "D_2") (pintype "input"))
      (node (ref "E15") (pin "7") (pinfunction "GND_7") (pintype "power_in"))
      (node (ref "E16") (pin "7") (pinfunction "GND_7") (pintype "power_in"))
      (node (ref "E17") (pin "7") (pinfunction "GND_7") (pintype "power_in"))
      (node (ref "E18") (pin "7") (pinfunction "GND_7") (pintype "power_in"))
      (node (ref "E19") (pin "7") (pinfunction "GND_7") (pintype "power_in"))
      (node (ref "E2") (pin "7") (pinfunction "GND_7") (pintype "power_in"))
      (node (ref "E3") (pin "7") (pinfunction "GND_7") (pintype "power_in"))
      (node (ref "E4") (pin "12") (pinfunction "GND_12") (pintype "power_in"))
      (node (ref "E5") (pin "2") (pinfunction "D_2") (pintype "input"))
      (node (ref "E5") (pin "7") (pinfunction "GND_7") (pintype "power_in"))
      (node (ref "E6") (pin "7") (pinfunction "GND_7") (pintype "power_in"))
      (node (ref "E7") (pin "7") (pinfunction "GND_7") (pintype "power_in"))
      (node (ref "E8") (pin "7") (pinfunction "GND_7") (pintype "power_in"))
      (node (ref "E8") (pin "9") (pinfunction "I_9") (pintype "input"))
      (node (ref "E9") (pin "7") (pinfunction "GND_7") (pintype "power_in"))
      (node (ref "R10") (pin "1") (pinfunction "1_1") (pintype "passive"))
      (node (ref "R4") (pin "1") (pinfunction "1_1") (pintype "passive"))
      (node (ref "R5") (pin "1") (pinfunction "1_1") (pintype "passive"))
      (node (ref "U$5") (pin "AC2") (pinfunction "1_AC2") (pintype "bidirectional"))
      (node (ref "U$5") (pin "BC2") (pinfunction "1_BC2") (pintype "bidirectional"))
      (node (ref "U$5") (pin "BT1") (pinfunction "1_BT1") (pintype "bidirectional"))
    )
    (net (code "70") (name "Net-(C16-Pad+)") (class "Default")
      (node (ref "C16") (pin "+") (pinfunction "+_+") (pintype "passive"))
      (node (ref "R11") (pin "2") (pinfunction "2_2") (pintype "passive"))
      (node (ref "R9") (pin "1") (pinfunction "1_1") (pintype "passive"))
    )
    (net (code "71") (name "Net-(C22-Pad+)") (class "Default")
      (node (ref "C22") (pin "+") (pinfunction "+_+") (pintype "passive"))
      (node (ref "D1") (pin "A") (pinfunction "A_A") (pintype "passive"))
      (node (ref "R1") (pin "1") (pinfunction "1_1") (pintype "passive"))
    )
    (net (code "72") (name "Net-(E1A-Q1)") (class "Default")
      (node (ref "E1") (pin "16") (pinfunction "Q1_16") (pintype "output"))
      (node (ref "E7") (pin "12") (pinfunction "I1_12") (pintype "input"))
    )
    (net (code "73") (name "Net-(E1A-Q3)") (class "Default")
      (node (ref "E1") (pin "10") (pinfunction "Q3_10") (pintype "output"))
      (node (ref "E7") (pin "5") (pinfunction "I0_5") (pintype "input"))
    )
    (net (code "74") (name "Net-(E2A-I1)") (class "Default")
      (node (ref "C19") (pin "1") (pinfunction "1_1") (pintype "passive"))
      (node (ref "D2") (pin "C") (pinfunction "C_C") (pintype "passive"))
      (node (ref "E2") (pin "2") (pinfunction "I1_2") (pintype "input"))
      (node (ref "R5") (pin "2") (pinfunction "2_2") (pintype "passive"))
    )
    (net (code "75") (name "Net-(E2B-I0)") (class "Default")
      (node (ref "E2") (pin "4") (pinfunction "I0_4") (pintype "input"))
      (node (ref "E3") (pin "8") (pinfunction "Q_8") (pintype "output"))
      (node (ref "E6") (pin "11") (pinfunction "I0_11") (pintype "input"))
    )
    (net (code "76") (name "Net-(E2B-O)") (class "Default")
      (node (ref "E2") (pin "6") (pinfunction "O_6") (pintype "output"))
      (node (ref "E2") (pin "9") (pinfunction "I0_9") (pintype "input"))
      (node (ref "E8") (pin "11") (pinfunction "I_11") (pintype "input"))
    )
    (net (code "77") (name "Net-(E2C-O)") (class "Default")
      (node (ref "E2") (pin "12") (pinfunction "I0_12") (pintype "input"))
      (node (ref "E2") (pin "8") (pinfunction "O_8") (pintype "output"))
    )
    (net (code "78") (name "Net-(E2D-O)") (class "Default")
      (node (ref "E2") (pin "11") (pinfunction "O_11") (pintype "output"))
      (node (ref "E8") (pin "1") (pinfunction "I_1") (pintype "input"))
    )
    (net (code "79") (name "Net-(E3A-P$5)") (class "Default")
      (node (ref "C22") (pin "-") (pinfunction "-_-") (pintype "passive"))
      (node (ref "E3") (pin "11") (pinfunction "P$5_11") (pintype "bidirectional"))
      (node (ref "E6") (pin "13") (pinfunction "O_13") (pintype "open_collector"))
    )
    (net (code "80") (name "Net-(E3A-P$6)") (class "Default")
      (node (ref "D1") (pin "C") (pinfunction "C_C") (pintype "passive"))
      (node (ref "E3") (pin "13") (pinfunction "P$6_13") (pintype "bidirectional"))
    )
    (net (code "81") (name "Net-(E4A-Q2)") (class "Default")
      (node (ref "E4") (pin "15") (pinfunction "Q2_15") (pintype "output"))
      (node (ref "E7") (pin "2") (pinfunction "I0_2") (pintype "input"))
    )
    (net (code "82") (name "Net-(E4A-Q3)") (class "Default")
      (node (ref "E4") (pin "10") (pinfunction "Q3_10") (pintype "output"))
      (node (ref "E7") (pin "9") (pinfunction "I1_9") (pintype "input"))
    )
    (net (code "83") (name "Net-(E6D-I1)") (class "Default")
      (node (ref "E6") (pin "12") (pinfunction "I1_12") (pintype "input"))
      (node (ref "E8") (pin "12") (pinfunction "O_12") (pintype "output"))
    )
    (net (code "84") (name "Net-(E9C-O)") (class "Default")
      (node (ref "C19") (pin "2") (pinfunction "2_2") (pintype "passive"))
      (node (ref "C24") (pin "1") (pinfunction "1_1") (pintype "passive"))
      (node (ref "E9") (pin "8") (pinfunction "O_8") (pintype "output"))
      (node (ref "R6") (pin "1") (pinfunction "1_1") (pintype "passive"))
    )
    (net (code "85") (name "Net-(E10A-O)") (class "Default")
      (node (ref "E10") (pin "12") (pinfunction "O_12") (pintype "output"))
      (node (ref "E15") (pin "10") (pinfunction "PRE_10") (pintype "input"))
    )
    (net (code "86") (name "Net-(E10C-O)") (class "Default")
      (node (ref "E10") (pin "8") (pinfunction "O_8") (pintype "output"))
      (node (ref "E8") (pin "5") (pinfunction "I_5") (pintype "input"))
    )
    (net (code "87") (name "Net-(E11A-I0)") (class "Default")
      (node (ref "E11") (pin "2") (pinfunction "I0_2") (pintype "input"))
      (node (ref "E4") (pin "16") (pinfunction "Q1_16") (pintype "output"))
    )
    (net (code "88") (name "Net-(E11B-I0)") (class "Default")
      (node (ref "E1") (pin "9") (pinfunction "Q4_9") (pintype "output"))
      (node (ref "E11") (pin "5") (pinfunction "I0_5") (pintype "input"))
    )
    (net (code "89") (name "Net-(E11C-I0)") (class "Default")
      (node (ref "E11") (pin "8") (pinfunction "I0_8") (pintype "input"))
      (node (ref "E4") (pin "9") (pinfunction "Q4_9") (pintype "output"))
    )
    (net (code "90") (name "Net-(E11D-I1)") (class "Default")
      (node (ref "E1") (pin "15") (pinfunction "Q2_15") (pintype "output"))
      (node (ref "E11") (pin "12") (pinfunction "I1_12") (pintype "input"))
    )
    (net (code "91") (name "Net-(E12A-I0)") (class "Default")
      (node (ref "E12") (pin "1") (pinfunction "I0_1") (pintype "input"))
      (node (ref "E12") (pin "2") (pinfunction "I1_2") (pintype "input"))
      (node (ref "E12") (pin "4") (pinfunction "I2_4") (pintype "input"))
      (node (ref "E12") (pin "5") (pinfunction "I3_5") (pintype "input"))
      (node (ref "R3") (pin "2") (pinfunction "2_2") (pintype "passive"))
    )
    (net (code "92") (name "Net-(E12B-I0)") (class "Default")
      (node (ref "E12") (pin "10") (pinfunction "I1_10") (pintype "input"))
      (node (ref "E12") (pin "12") (pinfunction "I2_12") (pintype "input"))
      (node (ref "E12") (pin "13") (pinfunction "I3_13") (pintype "input"))
      (node (ref "E12") (pin "9") (pinfunction "I0_9") (pintype "input"))
      (node (ref "E8") (pin "4") (pinfunction "O_4") (pintype "output"))
    )
    (net (code "93") (name "Net-(E13A-O)") (class "Default")
      (node (ref "E13") (pin "2") (pinfunction "O_2") (pintype "output"))
      (node (ref "E13") (pin "3") (pinfunction "I_3") (pintype "input"))
    )
    (net (code "94") (name "Net-(E13D-I)") (class "Default")
      (node (ref "E13") (pin "9") (pinfunction "I_9") (pintype "input"))
      (node (ref "E14") (pin "8") (pinfunction "O_8") (pintype "output"))
    )
    (net (code "95") (name "Net-(E13D-O)") (class "Default")
      (node (ref "E13") (pin "8") (pinfunction "O_8") (pintype "output"))
      (node (ref "E9") (pin "13") (pinfunction "I1_13") (pintype "input"))
      (node (ref "E9") (pin "2") (pinfunction "I1_2") (pintype "input"))
      (node (ref "E9") (pin "4") (pinfunction "I0_4") (pintype "input"))
    )
    (net (code "96") (name "Net-(E13F-I)") (class "Default")
      (node (ref "E13") (pin "13") (pinfunction "I_13") (pintype "input"))
      (node (ref "E9") (pin "3") (pinfunction "O_3") (pintype "output"))
    )
    (net (code "97") (name "Net-(E15A-~{Q})") (class "Default")
      (node (ref "E15") (pin "6") (pinfunction "~{Q}_6") (pintype "output"))
      (node (ref "E17") (pin "9") (pinfunction "I_9") (pintype "input"))
    )
    (net (code "98") (name "Net-(E16A-I1)") (class "Default")
      (node (ref "E16") (pin "2") (pinfunction "I1_2") (pintype "input"))
      (node (ref "E17") (pin "11") (pinfunction "I_11") (pintype "input"))
      (node (ref "E18") (pin "8") (pinfunction "~{Q}_8") (pintype "output"))
    )
    (net (code "99") (name "Net-(E16A-O)") (class "Default")
      (node (ref "E16") (pin "3") (pinfunction "O_3") (pintype "output"))
      (node (ref "E16") (pin "4") (pinfunction "I0_4") (pintype "input"))
    )
    (net (code "100") (name "Net-(E16B-I1)") (class "Default")
      (node (ref "E16") (pin "5") (pinfunction "I1_5") (pintype "input"))
      (node (ref "E19") (pin "6") (pinfunction "O_6") (pintype "output"))
    )
    (net (code "101") (name "Net-(E16D-O)") (class "Default")
      (node (ref "E16") (pin "11") (pinfunction "O_11") (pintype "output"))
      (node (ref "R3") (pin "1") (pinfunction "1_1") (pintype "passive"))
    )
    (net (code "102") (name "Net-(E17A-I)") (class "Default")
      (node (ref "E17") (pin "1") (pinfunction "I_1") (pintype "input"))
      (node (ref "E18") (pin "2") (pinfunction "D_2") (pintype "input"))
      (node (ref "E18") (pin "9") (pinfunction "Q_9") (pintype "output"))
      (node (ref "E19") (pin "4") (pinfunction "I0_4") (pintype "input"))
    )
    (net (code "103") (name "Net-(E17B-I)") (class "Default")
      (node (ref "E17") (pin "3") (pinfunction "I_3") (pintype "input"))
      (node (ref "E18") (pin "5") (pinfunction "Q_5") (pintype "output"))
      (node (ref "E19") (pin "5") (pinfunction "I1_5") (pintype "input"))
    )
    (net (code "104") (name "Net-(E17F-I)") (class "Default")
      (node (ref "E17") (pin "13") (pinfunction "I_13") (pintype "input"))
      (node (ref "Q1") (pin "2") (pinfunction "B_2") (pintype "passive"))
      (node (ref "Q2") (pin "3") (pinfunction "C_3") (pintype "passive"))
      (node (ref "R12") (pin "1") (pinfunction "1_1") (pintype "passive"))
    )
    (net (code "105") (name "Net-(E17F-O)") (class "Default")
      (node (ref "E17") (pin "12") (pinfunction "O_12") (pintype "output"))
      (node (ref "E19") (pin "10") (pinfunction "I1_10") (pintype "input"))
      (node (ref "E3") (pin "1") (pinfunction "P$1_1") (pintype "input"))
      (node (ref "E3") (pin "2") (pinfunction "P$2_2") (pintype "input"))
      (node (ref "R15") (pin "1") (pinfunction "1_1") (pintype "passive"))
      (node (ref "R16") (pin "1") (pinfunction "1_1") (pintype "passive"))
    )
    (net (code "106") (name "Net-(E19C-I0)") (class "Default")
      (node (ref "E19") (pin "11") (pinfunction "O_11") (pintype "output"))
      (node (ref "E19") (pin "9") (pinfunction "I0_9") (pintype "input"))
      (node (ref "E8") (pin "13") (pinfunction "I_13") (pintype "input"))
    )
    (net (code "107") (name "Net-(E19C-O)") (class "Default")
      (node (ref "E19") (pin "12") (pinfunction "I0_12") (pintype "input"))
      (node (ref "E19") (pin "8") (pinfunction "O_8") (pintype "output"))
    )
    (net (code "108") (name "Net-(Q1-C)") (class "Default")
      (node (ref "Q1") (pin "3") (pinfunction "C_3") (pintype "passive"))
      (node (ref "R13") (pin "1") (pinfunction "1_1") (pintype "passive"))
    )
    (net (code "109") (name "Net-(Q1-E)") (class "Default")
      (node (ref "Q1") (pin "1") (pinfunction "E_1") (pintype "passive"))
      (node (ref "Q2") (pin "1") (pinfunction "E_1") (pintype "passive"))
      (node (ref "R10") (pin "2") (pinfunction "2_2") (pintype "passive"))
    )
    (net (code "110") (name "Net-(Q2-B)") (class "Default")
      (node (ref "Q2") (pin "2") (pinfunction "B_2") (pintype "passive"))
      (node (ref "R9") (pin "2") (pinfunction "2_2") (pintype "passive"))
    )
    (net (code "111") (name "unconnected-(E1A-~{Q1}-Pad1)") (class "Default")
      (node (ref "E1") (pin "1") (pinfunction "~{Q1}_1") (pintype "output"))
    )
    (net (code "112") (name "unconnected-(E1A-~{Q2}-Pad14)") (class "Default")
      (node (ref "E1") (pin "14") (pinfunction "~{Q2}_14") (pintype "output"))
    )
    (net (code "113") (name "unconnected-(E1A-~{Q3}-Pad11)") (class "Default")
      (node (ref "E1") (pin "11") (pinfunction "~{Q3}_11") (pintype "output"))
    )
    (net (code "114") (name "unconnected-(E1A-~{Q4}-Pad8)") (class "Default")
      (node (ref "E1") (pin "8") (pinfunction "~{Q4}_8") (pintype "output"))
    )
    (net (code "115") (name "unconnected-(E3A-~{Q}-Pad6)") (class "Default")
      (node (ref "E3") (pin "6") (pinfunction "~{Q}_6") (pintype "output"))
    )
    (net (code "116") (name "unconnected-(E4A-~{Q1}-Pad1)") (class "Default")
      (node (ref "E4") (pin "1") (pinfunction "~{Q1}_1") (pintype "output"))
    )
    (net (code "117") (name "unconnected-(E4A-~{Q2}-Pad14)") (class "Default")
      (node (ref "E4") (pin "14") (pinfunction "~{Q2}_14") (pintype "output"))
    )
    (net (code "118") (name "unconnected-(E4A-~{Q3}-Pad11)") (class "Default")
      (node (ref "E4") (pin "11") (pinfunction "~{Q3}_11") (pintype "output"))
    )
    (net (code "119") (name "unconnected-(E4A-~{Q4}-Pad8)") (class "Default")
      (node (ref "E4") (pin "8") (pinfunction "~{Q4}_8") (pintype "output"))
    )
    (net (code "120") (name "unconnected-(E5B-~{Q}-Pad8)") (class "Default")
      (node (ref "E5") (pin "8") (pinfunction "~{Q}_8") (pintype "output"))
    )
    (net (code "121") (name "unconnected-(E8D-O-Pad8)") (class "Default")
      (node (ref "E8") (pin "8") (pinfunction "O_8") (pintype "output"))
    )
    (net (code "122") (name "unconnected-(E12B-O-Pad8)") (class "Default")
      (node (ref "E12") (pin "8") (pinfunction "O_8") (pintype "output"))
    )
    (net (code "123") (name "unconnected-(E15A-Q-Pad5)") (class "Default")
      (node (ref "E15") (pin "5") (pinfunction "Q_5") (pintype "output"))
    )
  )
)
